# Iridium_9603_Beacon.net
KiCad netlist of a schematic drawn in EAGLE
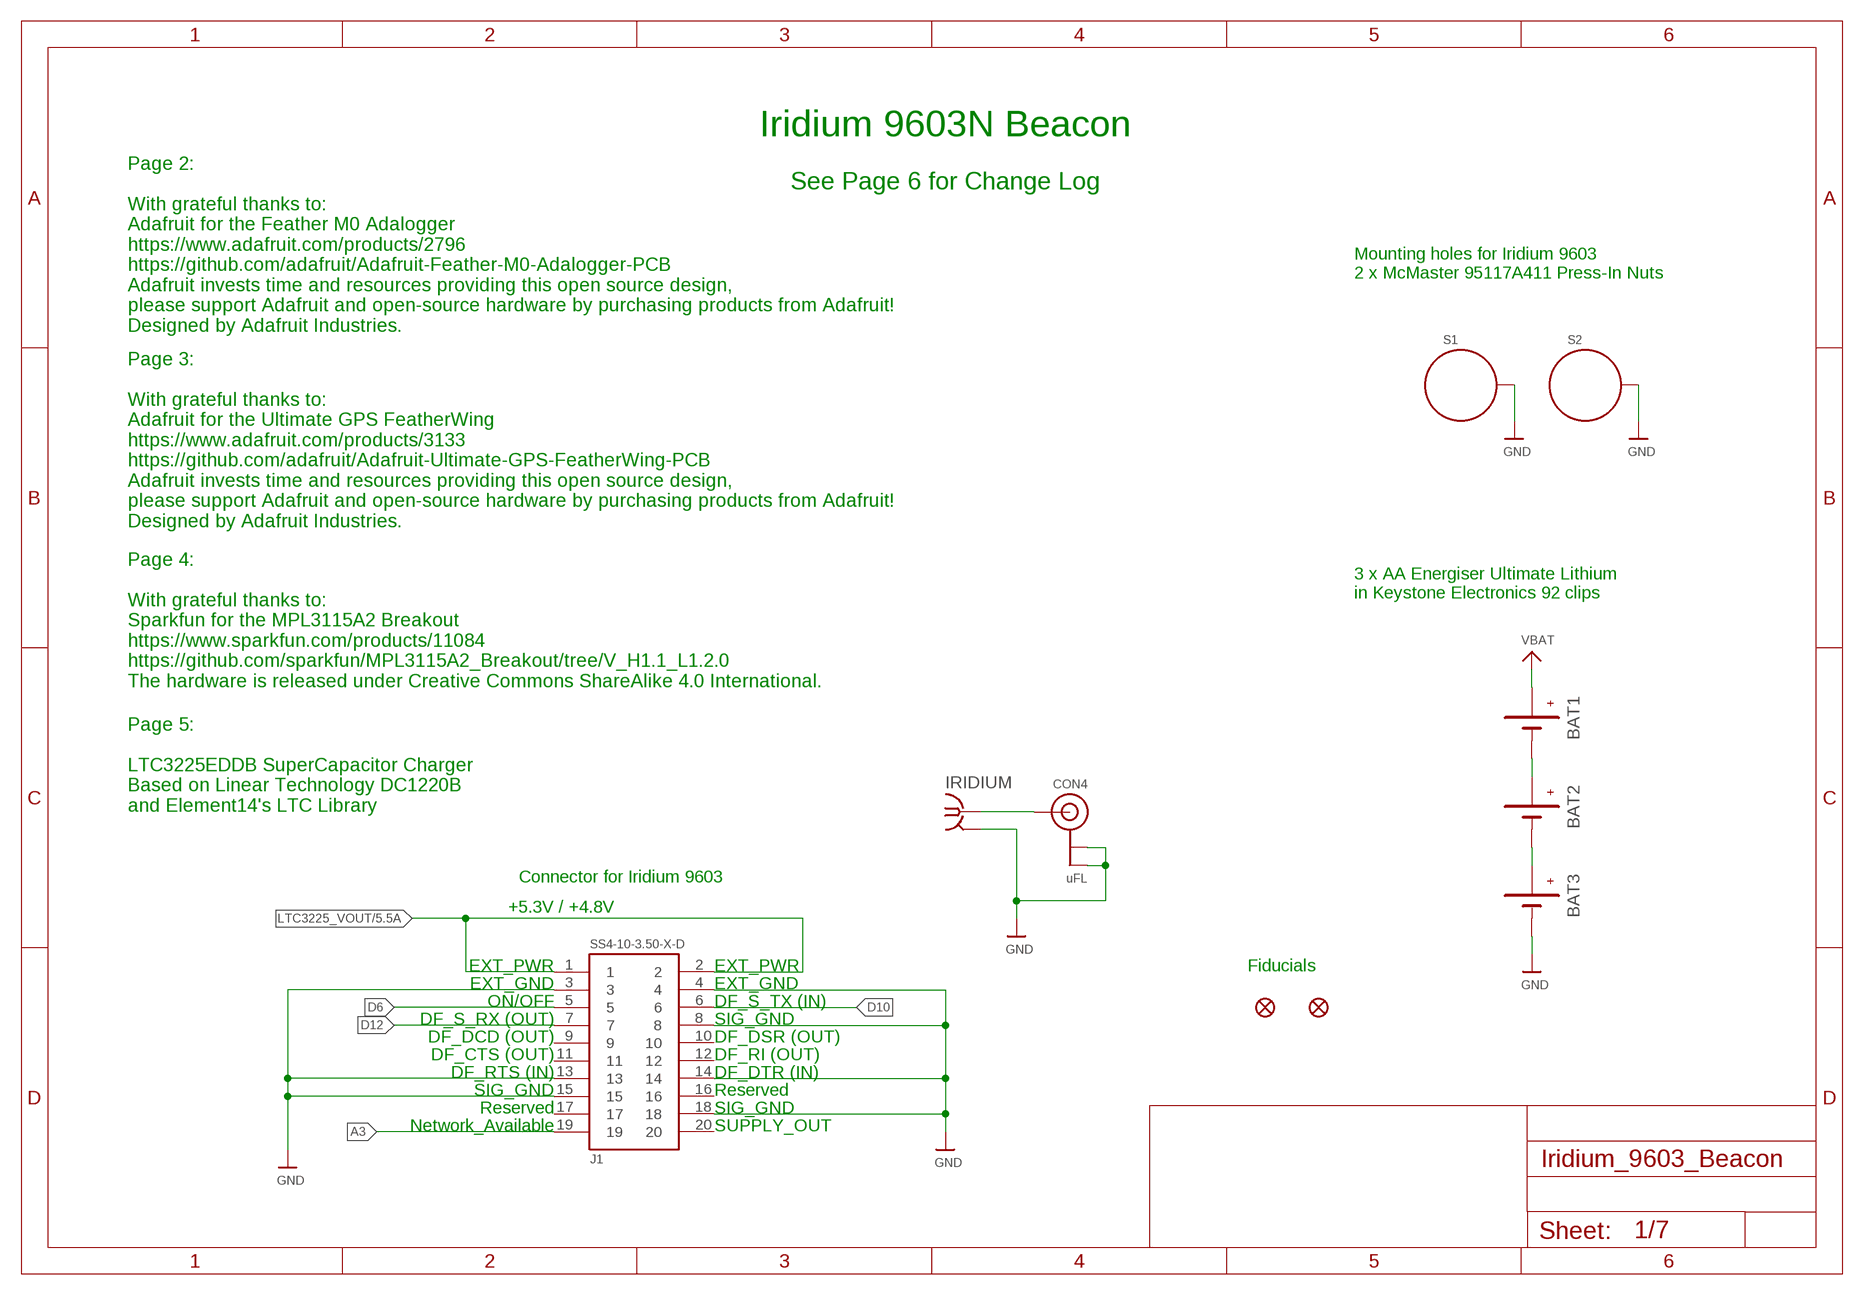
[diagram p0: schematic, sheet 1]
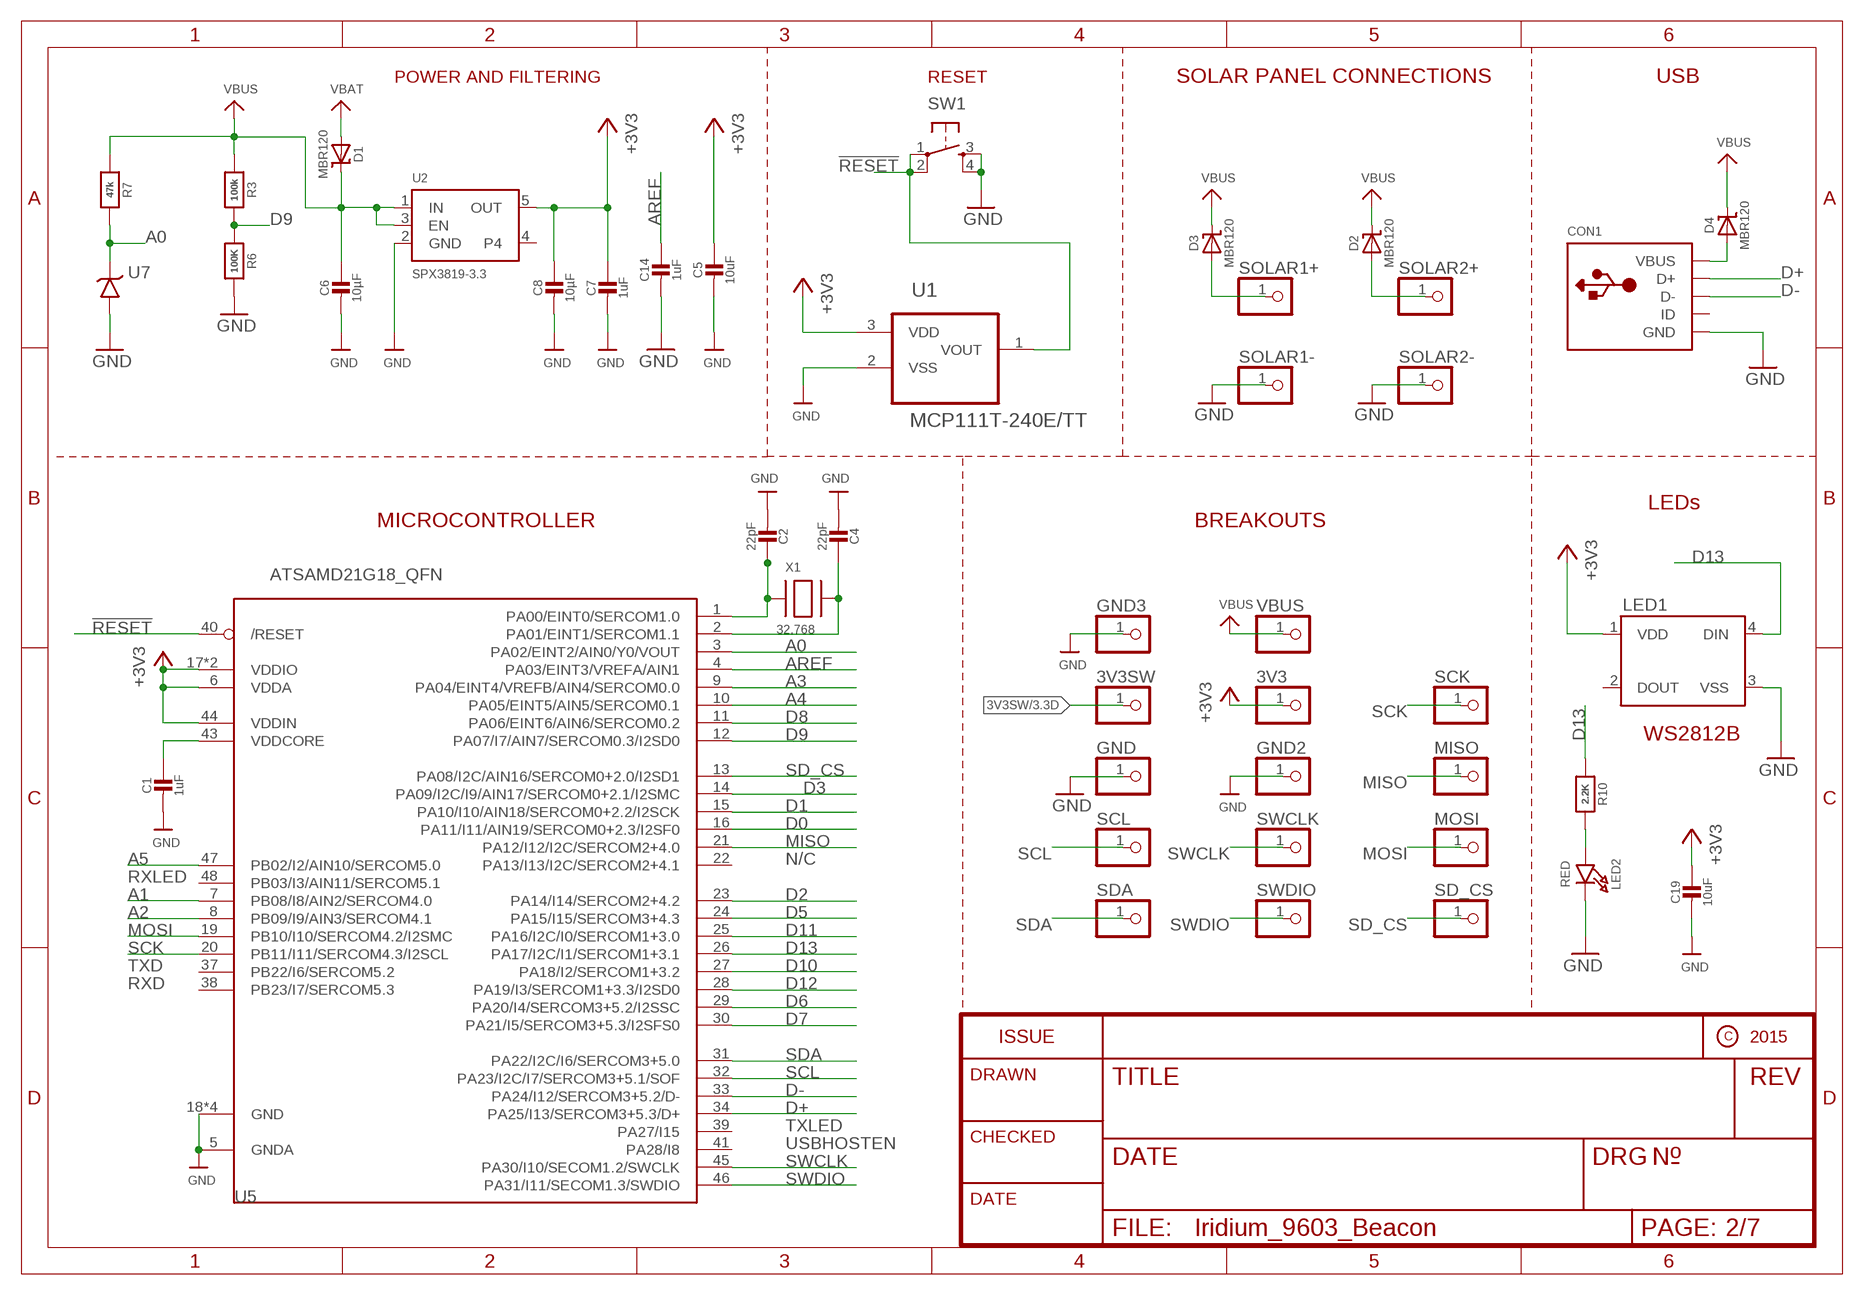
[diagram p1: schematic, sheet 2]
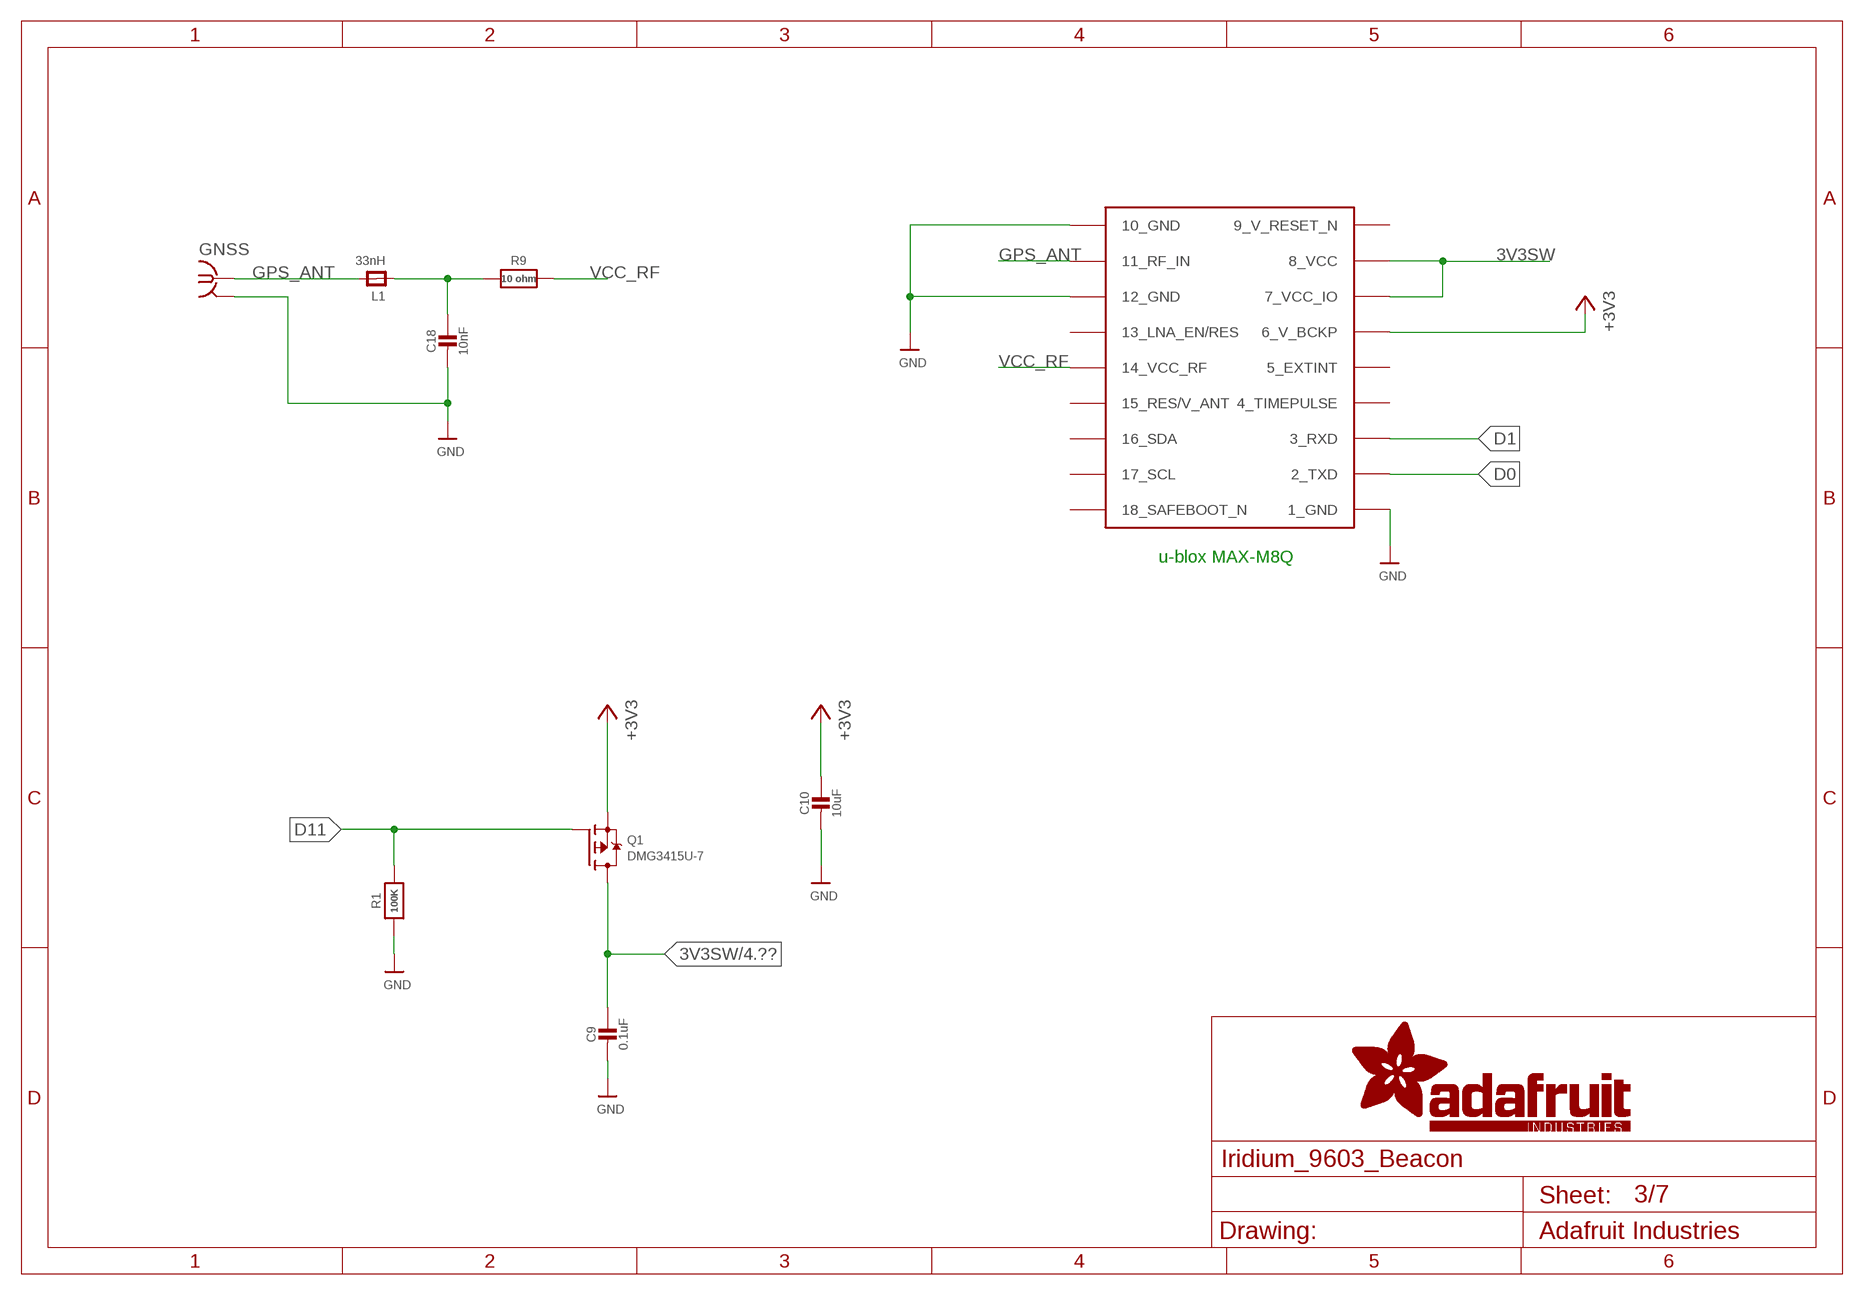
[diagram p2: schematic, sheet 3]
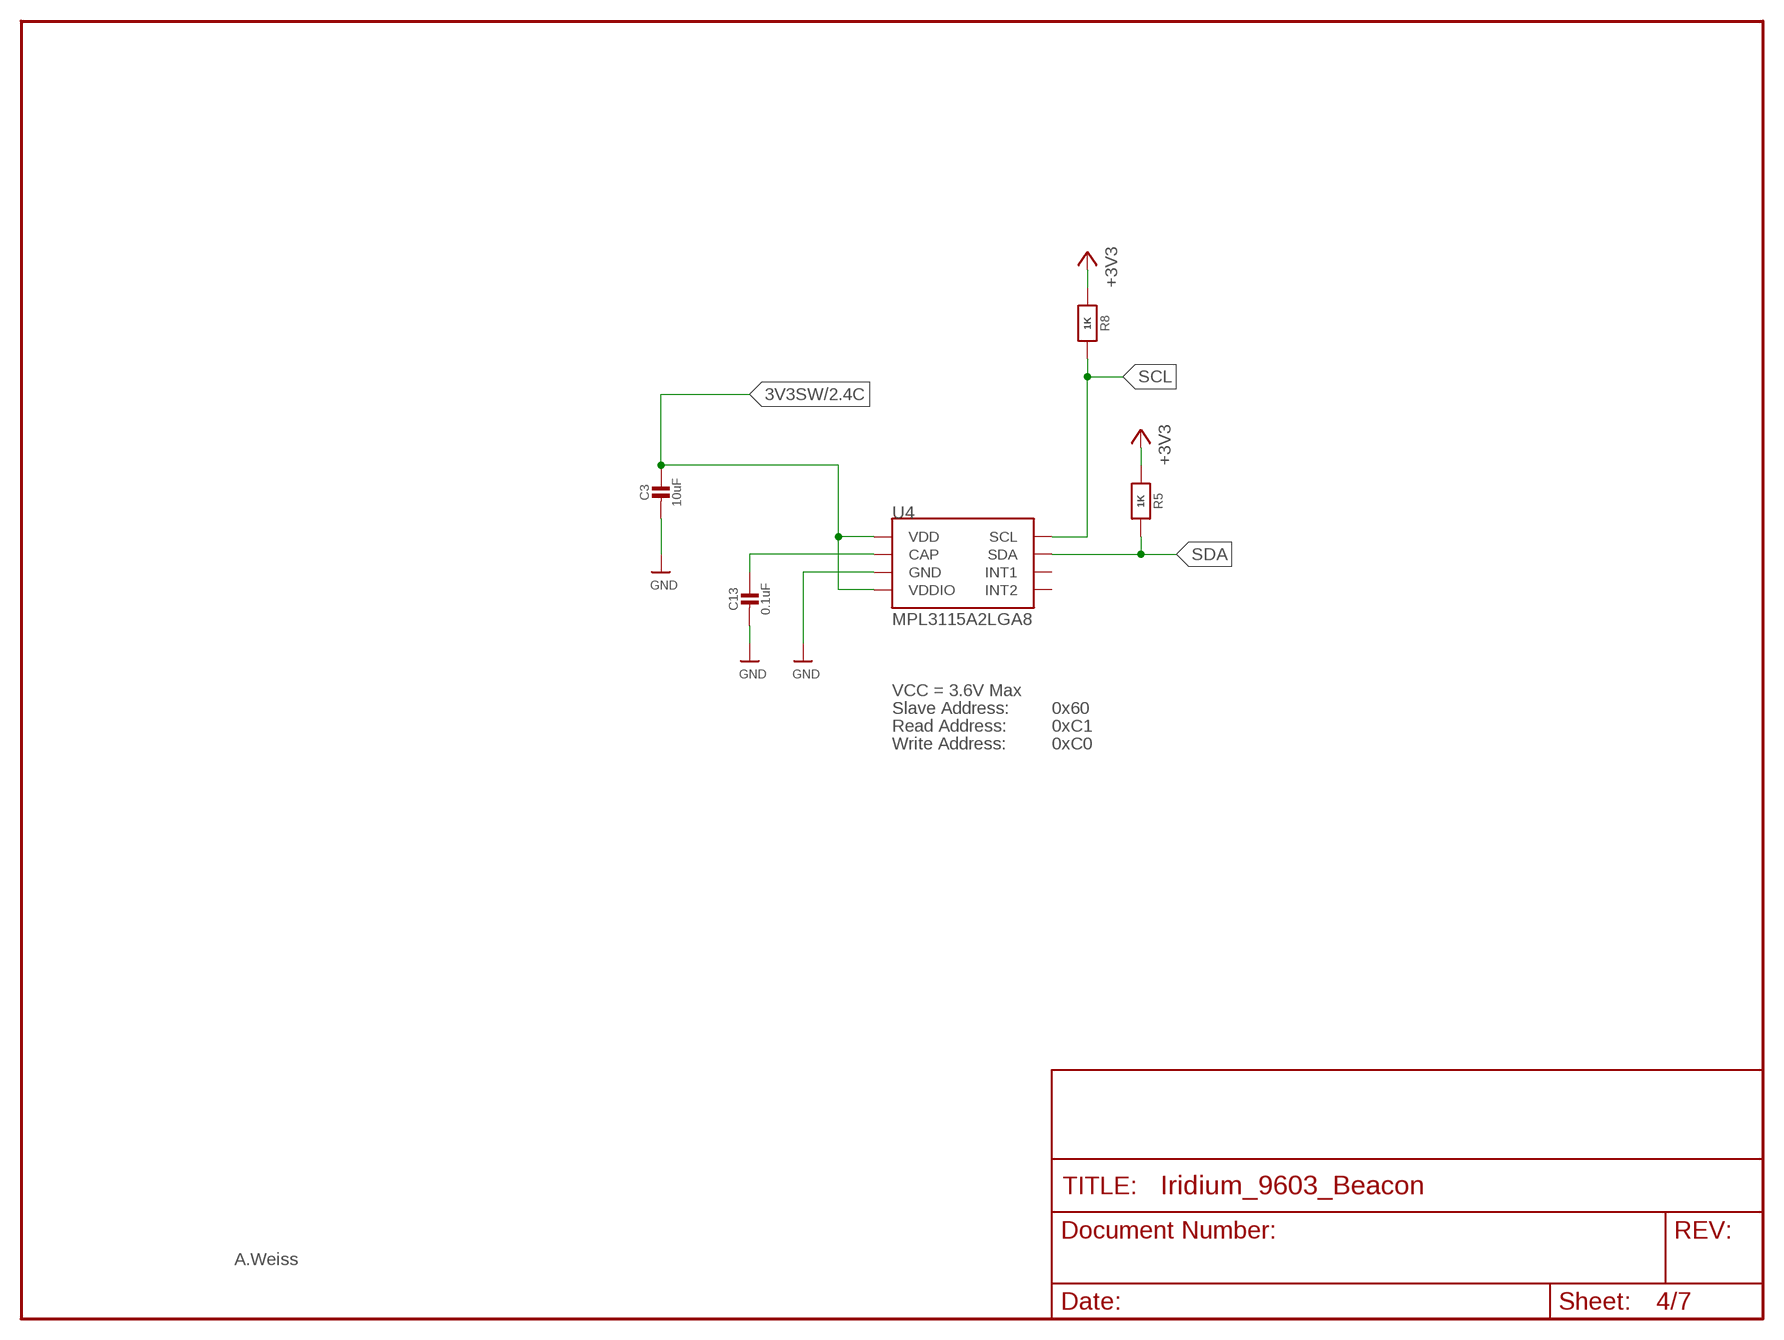
[diagram p3: schematic, sheet 4]
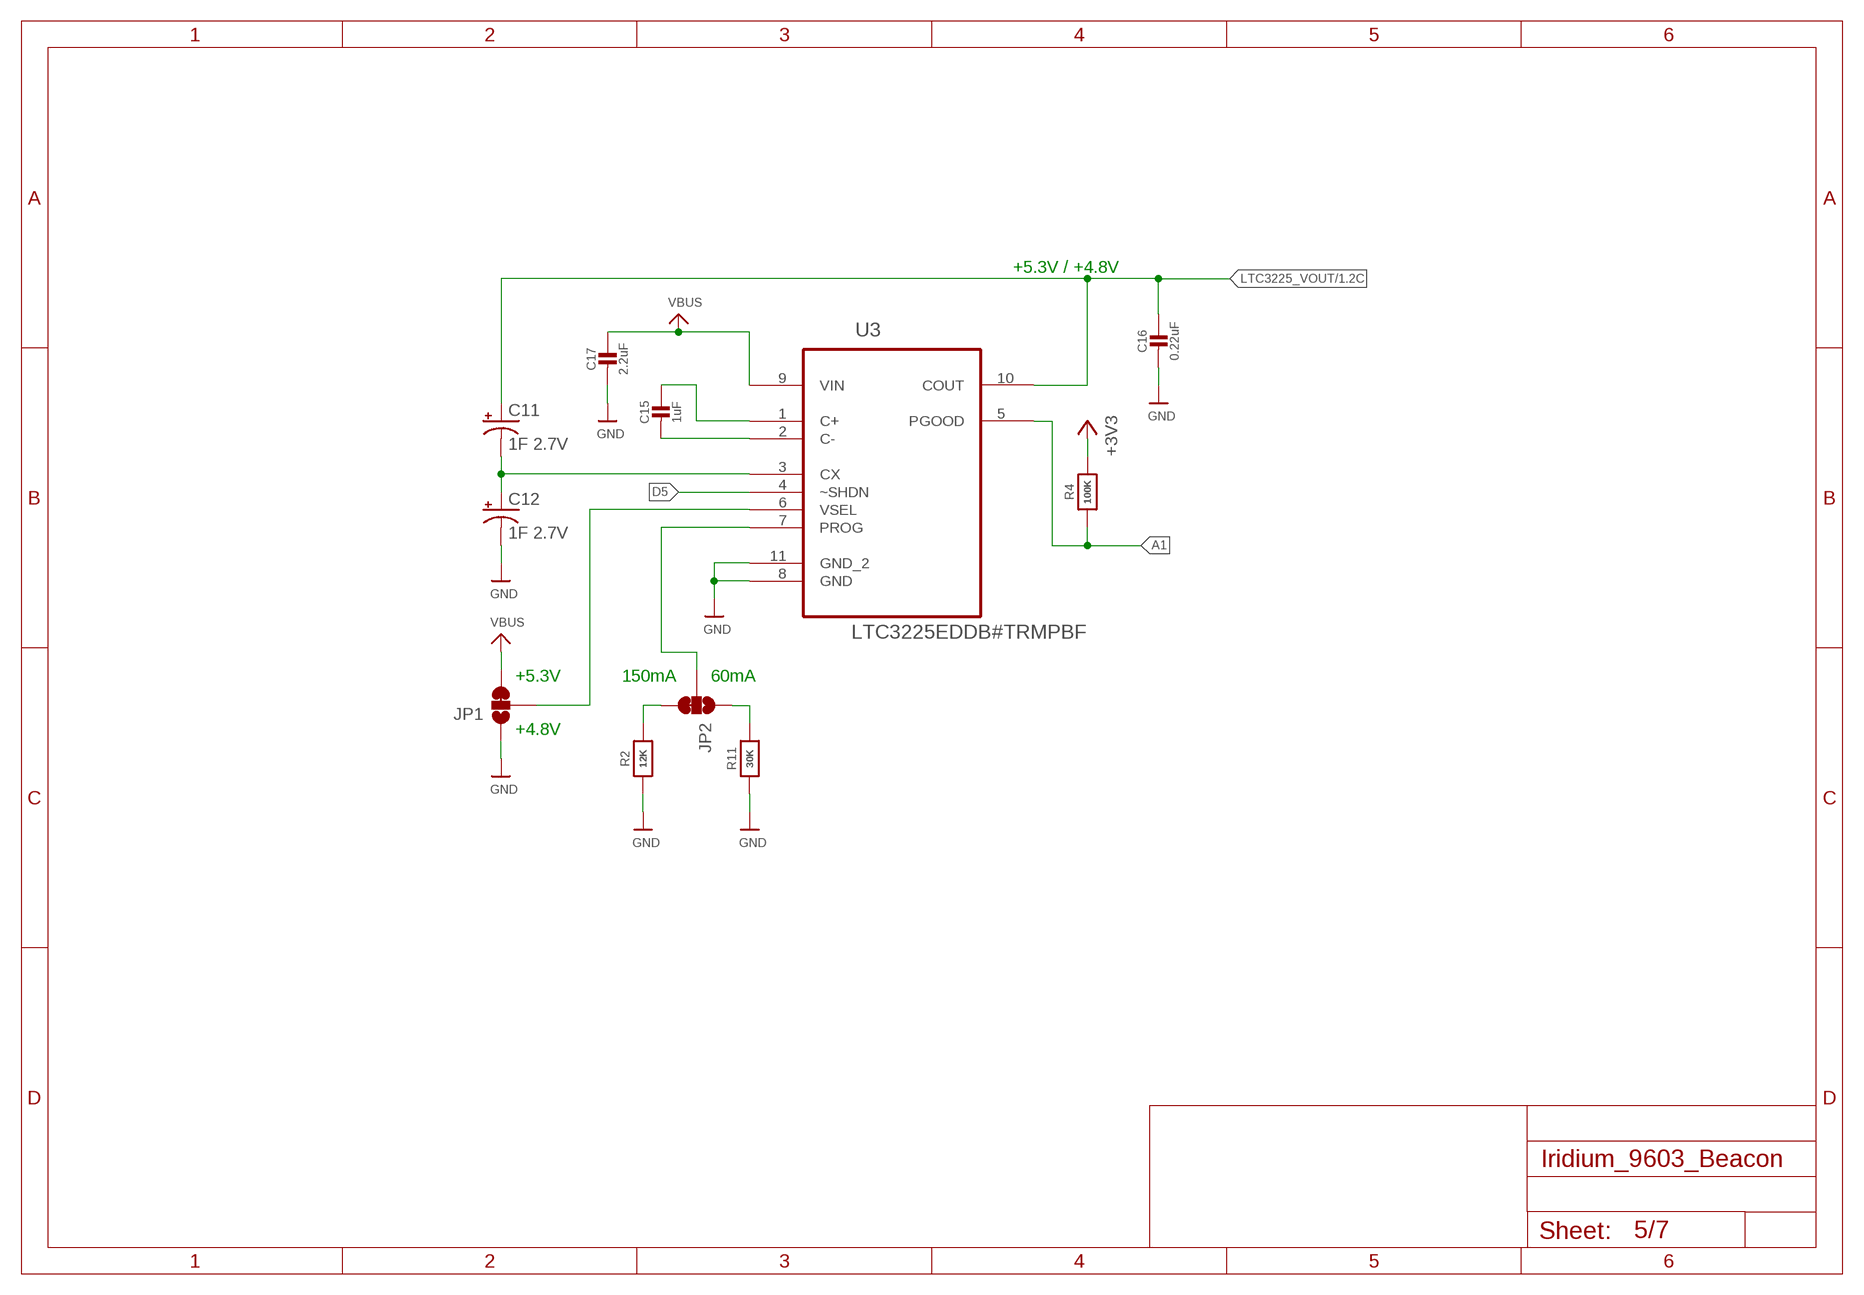
[diagram p4: schematic, sheet 5]
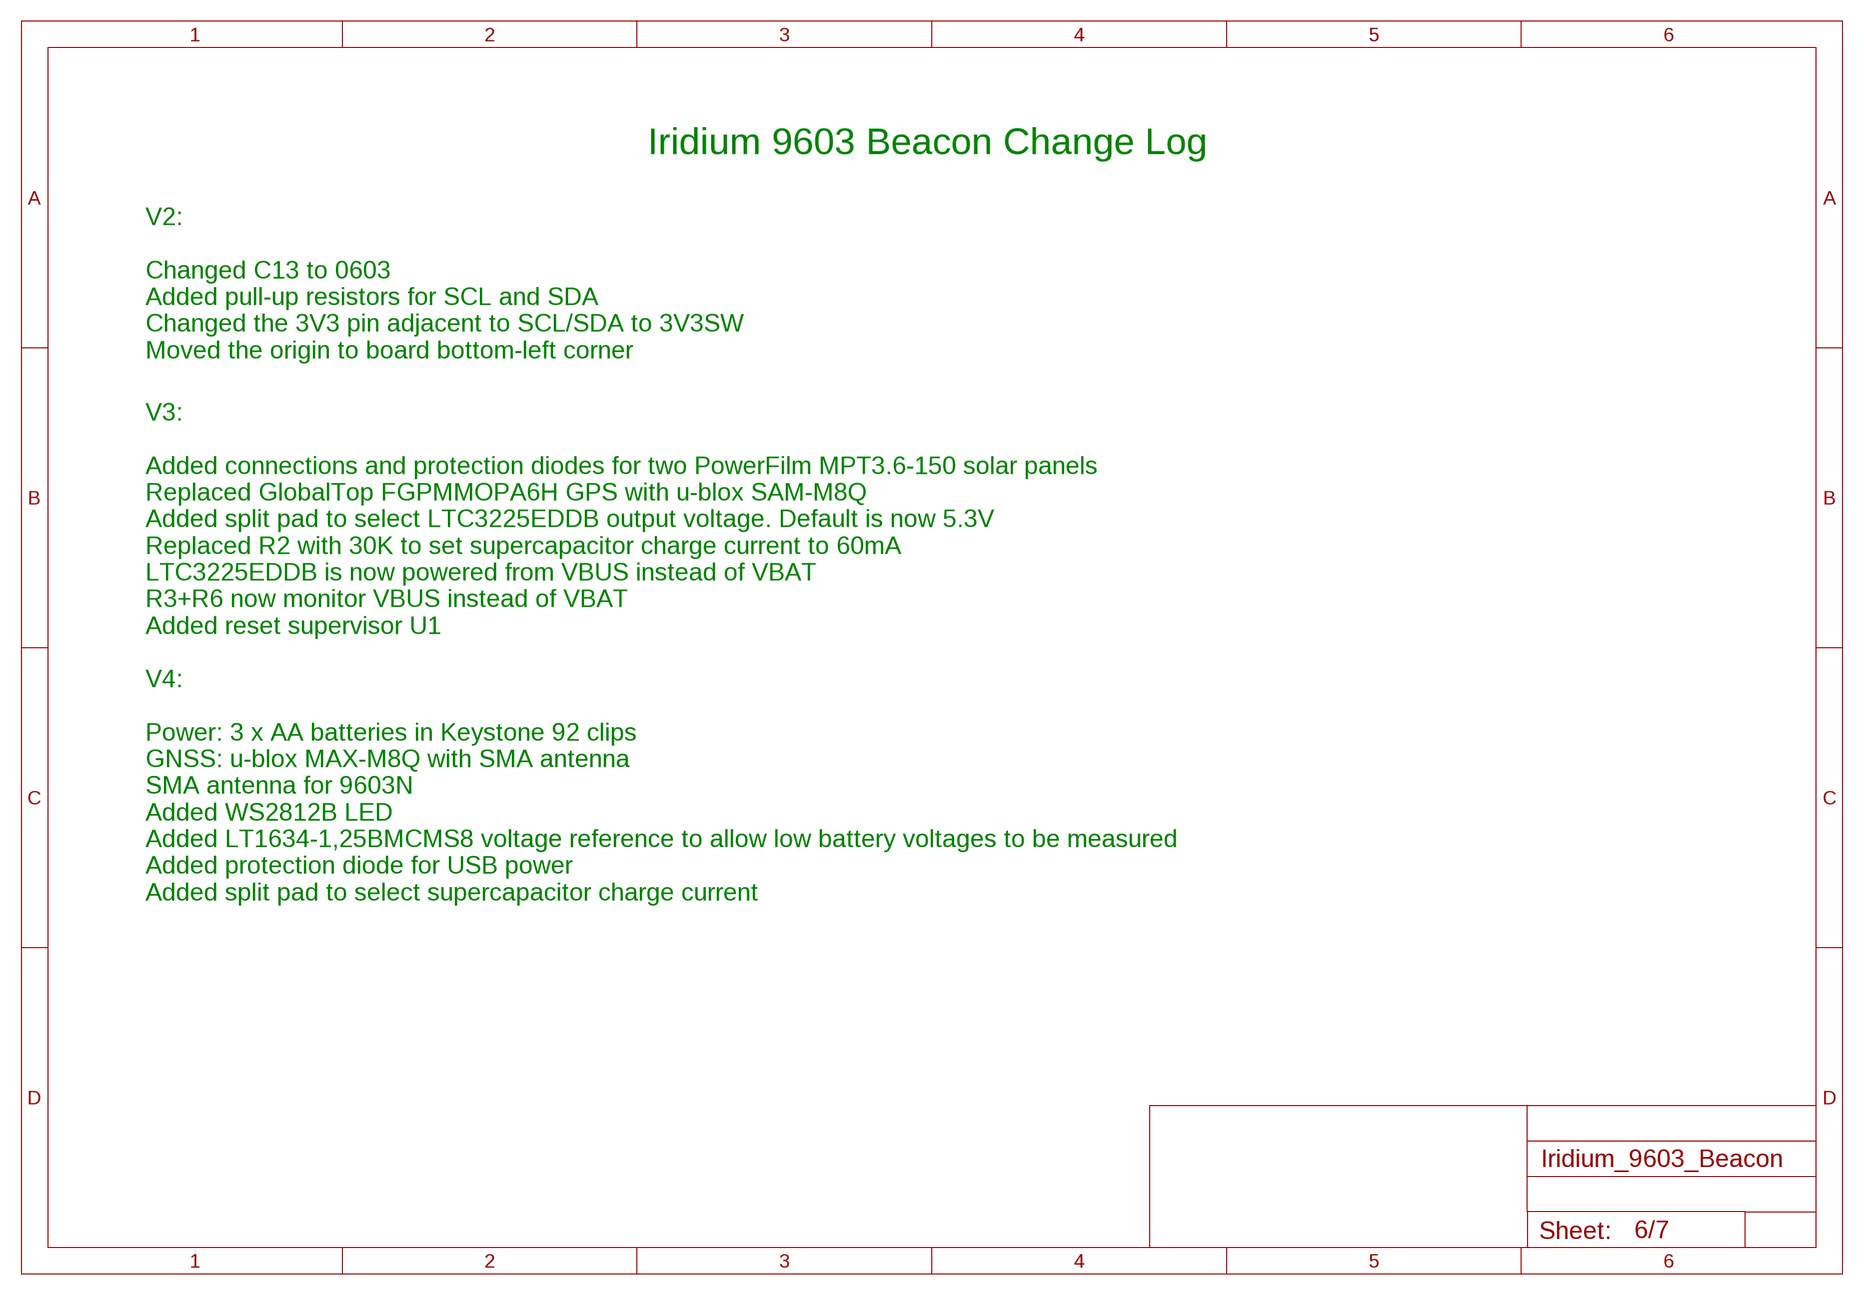
[diagram p5: schematic, sheet 6]
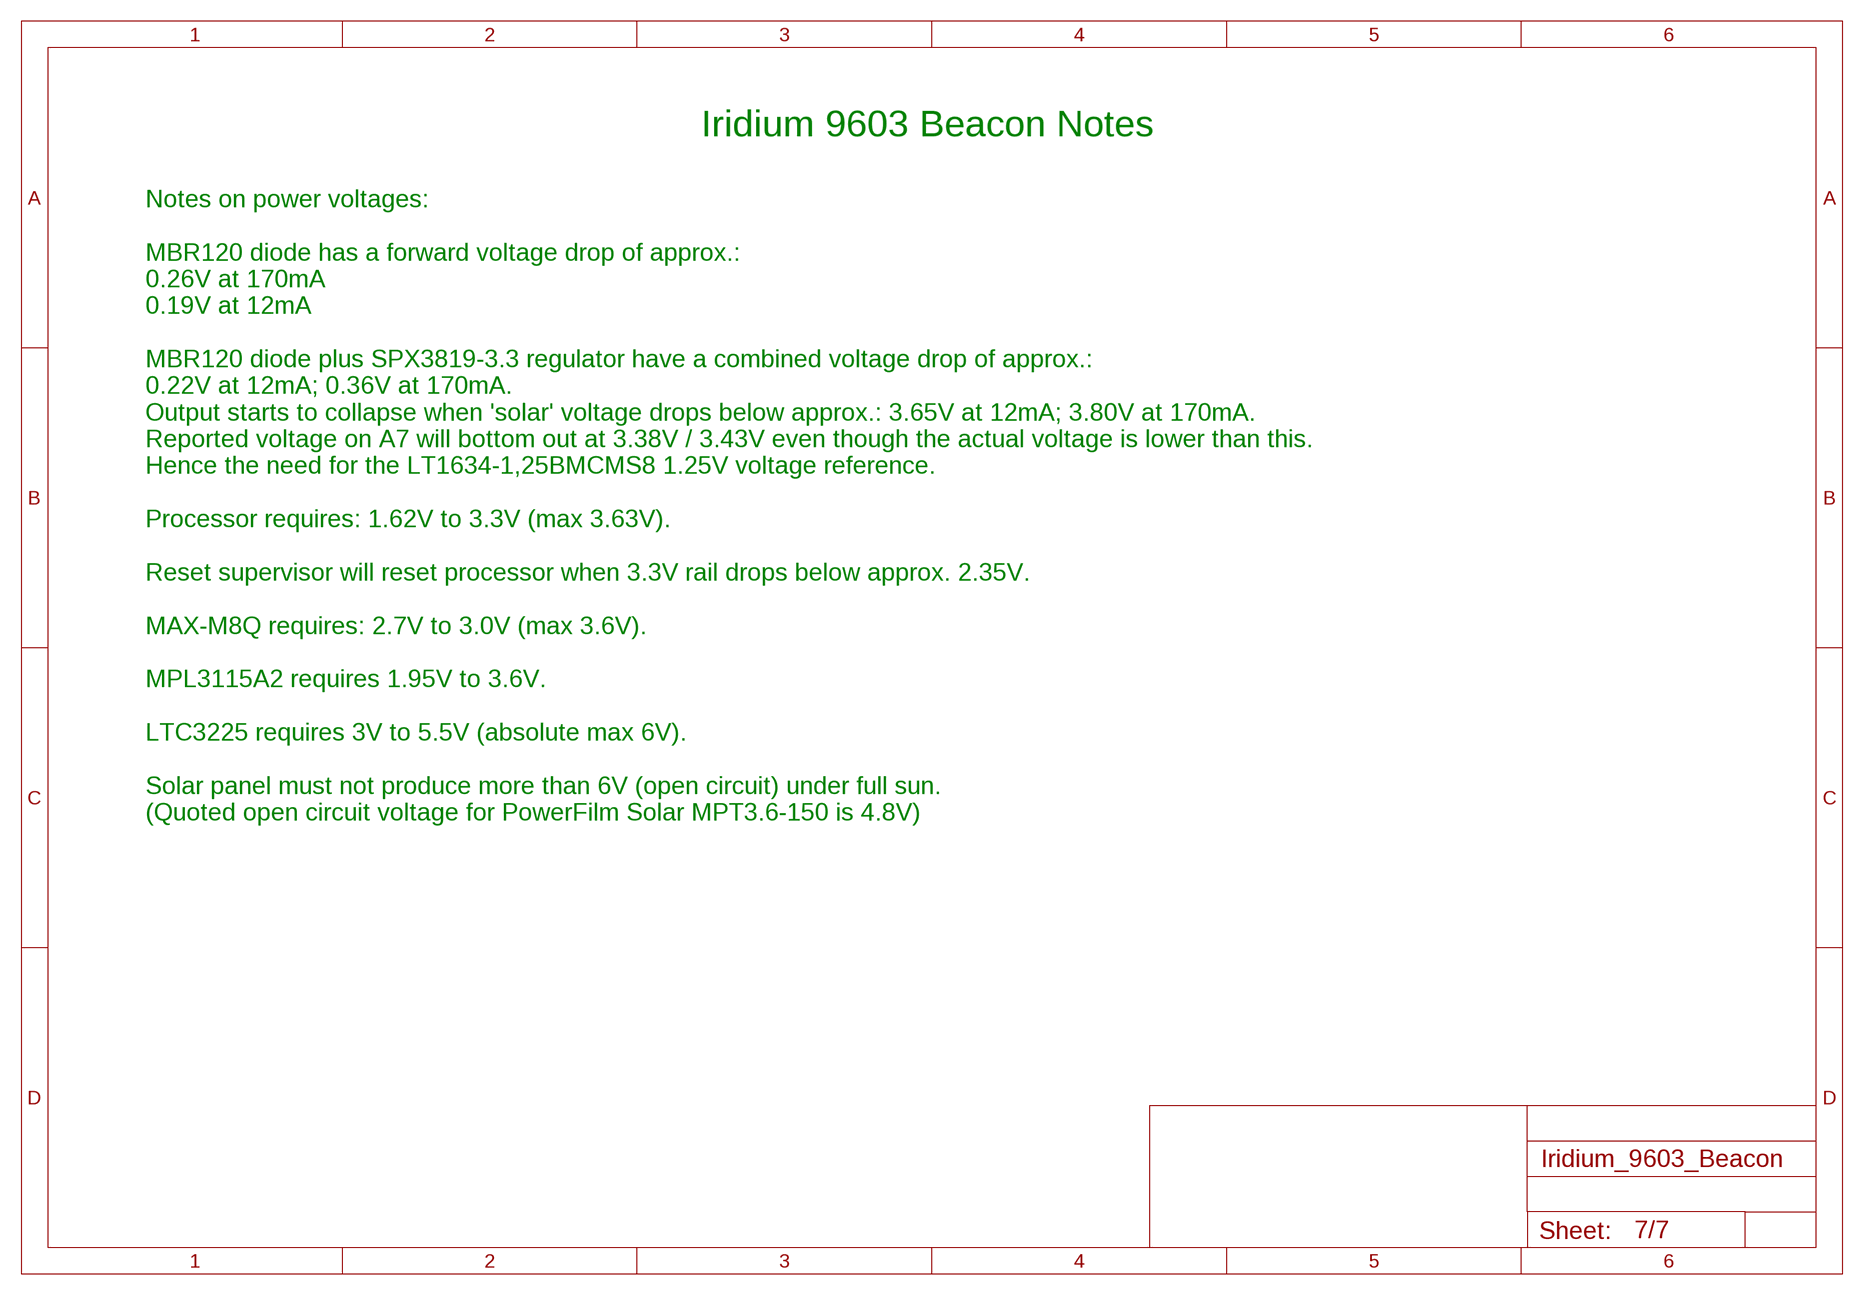
[diagram p6: schematic, sheet 7]

(export (version "E")
  (design (tool "Eeschema 10.0.6"))
  (components
    (comp (ref "3V3")
      (value "PINHD-1X1")
      (footprint "eagle-import:1X01")
      (libsource (lib "eagle-import") (part "PINHD-1X1"))
    )
    (comp (ref "3V3SW")
      (value "PINHD-1X1")
      (footprint "eagle-import:1X01")
      (libsource (lib "eagle-import") (part "PINHD-1X1"))
    )
    (comp (ref "C1")
      (value "1uF")
      (footprint "eagle-import:0603-NO")
      (libsource (lib "eagle-import") (part "CAP_CERAMIC0603_NO"))
    )
    (comp (ref "C2")
      (value "22pF")
      (footprint "eagle-import:0603-NO")
      (libsource (lib "eagle-import") (part "CAP_CERAMIC0603_NO"))
    )
    (comp (ref "C4")
      (value "22pF")
      (footprint "eagle-import:0603-NO")
      (libsource (lib "eagle-import") (part "CAP_CERAMIC0603_NO"))
    )
    (comp (ref "C5")
      (value "10uF")
      (footprint "eagle-import:0805-NO")
      (libsource (lib "eagle-import") (part "CAP_CERAMIC0805-NOOUTLINE"))
    )
    (comp (ref "C6")
      (value "10µF")
      (footprint "eagle-import:0805-NO")
      (libsource (lib "eagle-import") (part "CAP_CERAMIC0805-NOOUTLINE"))
    )
    (comp (ref "C7")
      (value "1uF")
      (footprint "eagle-import:0603-NO")
      (libsource (lib "eagle-import") (part "CAP_CERAMIC0603_NO"))
    )
    (comp (ref "C8")
      (value "10µF")
      (footprint "eagle-import:0805-NO")
      (libsource (lib "eagle-import") (part "CAP_CERAMIC0805-NOOUTLINE"))
    )
    (comp (ref "C14")
      (value "1uF")
      (footprint "eagle-import:0603-NO")
      (libsource (lib "eagle-import") (part "CAP_CERAMIC0603_NO"))
    )
    (comp (ref "C19")
      (value "10uF")
      (footprint "eagle-import:0805-NO")
      (libsource (lib "eagle-import") (part "CAP_CERAMIC0805-NOOUTLINE"))
    )
    (comp (ref "CON1")
      (value "USBFCI_10103594")
      (footprint "eagle-import:FCI_10103594")
      (libsource (lib "eagle-import") (part "USBFCI_10103594"))
    )
    (comp (ref "D1")
      (value "MBR120")
      (footprint "eagle-import:SOD-123")
      (libsource (lib "eagle-import") (part "DIODE-SCHOTTKYSOD-123"))
    )
    (comp (ref "D2")
      (value "MBR120")
      (footprint "eagle-import:SOD-123")
      (libsource (lib "eagle-import") (part "DIODE-SCHOTTKYSOD-123"))
    )
    (comp (ref "D3")
      (value "MBR120")
      (footprint "eagle-import:SOD-123")
      (libsource (lib "eagle-import") (part "DIODE-SCHOTTKYSOD-123"))
    )
    (comp (ref "D4")
      (value "MBR120")
      (footprint "eagle-import:SOD-123")
      (libsource (lib "eagle-import") (part "DIODE-SCHOTTKYSOD-123"))
    )
    (comp (ref "GND")
      (value "PINHD-1X1")
      (footprint "eagle-import:1X01")
      (libsource (lib "eagle-import") (part "PINHD-1X1"))
    )
    (comp (ref "GND2")
      (value "PINHD-1X1")
      (footprint "eagle-import:1X01")
      (libsource (lib "eagle-import") (part "PINHD-1X1"))
    )
    (comp (ref "GND3")
      (value "PINHD-1X1")
      (footprint "eagle-import:1X01")
      (libsource (lib "eagle-import") (part "PINHD-1X1"))
    )
    (comp (ref "LED1")
      (value "WS2812B")
      (footprint "eagle-import:WS2812B")
      (libsource (lib "eagle-import") (part "WS2812B"))
    )
    (comp (ref "LED2")
      (value "RED")
      (footprint "eagle-import:CHIPLED_0805_NOOUTLINE")
      (libsource (lib "eagle-import") (part "LED0805_NOOUTLINE"))
    )
    (comp (ref "MISO")
      (value "PINHD-1X1")
      (footprint "eagle-import:1X01")
      (libsource (lib "eagle-import") (part "PINHD-1X1"))
    )
    (comp (ref "MOSI")
      (value "PINHD-1X1")
      (footprint "eagle-import:1X01")
      (libsource (lib "eagle-import") (part "PINHD-1X1"))
    )
    (comp (ref "R3")
      (value "100k")
      (footprint "eagle-import:0603-NO")
      (libsource (lib "eagle-import") (part "RESISTOR_0603_NOOUT"))
    )
    (comp (ref "R6")
      (value "100K")
      (footprint "eagle-import:0603-NO")
      (libsource (lib "eagle-import") (part "RESISTOR_0603_NOOUT"))
    )
    (comp (ref "R7")
      (value "47k")
      (footprint "eagle-import:0603-NO")
      (libsource (lib "eagle-import") (part "RESISTOR_0603_NOOUT"))
    )
    (comp (ref "R10")
      (value "2.2K")
      (footprint "eagle-import:0603-NO")
      (libsource (lib "eagle-import") (part "RESISTOR_0603_NOOUT"))
    )
    (comp (ref "SCK")
      (value "PINHD-1X1")
      (footprint "eagle-import:1X01")
      (libsource (lib "eagle-import") (part "PINHD-1X1"))
    )
    (comp (ref "SCL")
      (value "PINHD-1X1")
      (footprint "eagle-import:1X01")
      (libsource (lib "eagle-import") (part "PINHD-1X1"))
    )
    (comp (ref "SDA")
      (value "PINHD-1X1")
      (footprint "eagle-import:1X01")
      (libsource (lib "eagle-import") (part "PINHD-1X1"))
    )
    (comp (ref "SD_CS")
      (value "PINHD-1X1")
      (footprint "eagle-import:1X01")
      (libsource (lib "eagle-import") (part "PINHD-1X1"))
    )
    (comp (ref "SOLAR1+")
      (value "PINHD-1X1")
      (footprint "eagle-import:1X01")
      (libsource (lib "eagle-import") (part "PINHD-1X1"))
    )
    (comp (ref "SOLAR1-")
      (value "PINHD-1X1")
      (footprint "eagle-import:1X01")
      (libsource (lib "eagle-import") (part "PINHD-1X1"))
    )
    (comp (ref "SOLAR2+")
      (value "PINHD-1X1")
      (footprint "eagle-import:1X01")
      (libsource (lib "eagle-import") (part "PINHD-1X1"))
    )
    (comp (ref "SOLAR2-")
      (value "PINHD-1X1")
      (footprint "eagle-import:1X01")
      (libsource (lib "eagle-import") (part "PINHD-1X1"))
    )
    (comp (ref "SW1")
      (value "SWITCH_SPST_4_PINRECT")
      (footprint "eagle-import:TACTILE_SWITCH_SMD_4.6X2.8MM")
      (libsource (lib "eagle-import") (part "SWITCH_SPST_4_PINRECT"))
    )
    (comp (ref "SWCLK")
      (value "PINHD-1X1")
      (footprint "eagle-import:1X01")
      (libsource (lib "eagle-import") (part "PINHD-1X1"))
    )
    (comp (ref "SWDIO")
      (value "PINHD-1X1")
      (footprint "eagle-import:1X01")
      (libsource (lib "eagle-import") (part "PINHD-1X1"))
    )
    (comp (ref "U1")
      (value "MCP111T-240E/TT")
      (footprint "eagle-import:SOT95P237X112-3N")
      (fields (field (name "MPN") "MCP111T-270E/TT") (field (name "MPN_1") "MCP111T-240E/TT"))
      (libsource (lib "eagle-import") (part "MCP111T-270E/TT"))
    )
    (comp (ref "U2")
      (value "SPX3819-3.3")
      (footprint "eagle-import:SOT23-5")
      (libsource (lib "eagle-import") (part "VREG_SOT23-5"))
    )
    (comp (ref "U5")
      (value "ATSAMD21G18_QFN")
      (footprint "eagle-import:TQFN48_7MM")
      (libsource (lib "eagle-import") (part "ATSAMD21J_QFN"))
    )
    (comp (ref "U7")
      (value "LT1634-1,25BMCMS8")
      (footprint "eagle-import:MSOP8")
      (libsource (lib "eagle-import") (part "LT1634BMCMS8-1,25"))
    )
    (comp (ref "VBUS")
      (value "PINHD-1X1")
      (footprint "eagle-import:1X01")
      (libsource (lib "eagle-import") (part "PINHD-1X1"))
    )
    (comp (ref "X1")
      (value "32.768")
      (footprint "eagle-import:XTAL3215")
      (libsource (lib "eagle-import") (part "XTAL-3.2X1.5"))
    )
    (comp (ref "BAT1")
      (value "BATTERYKEYSTONE92")
      (footprint "eagle-import:BATTERY-AAA-KEYSTONE92")
      (libsource (lib "eagle-import") (part "BATTERYKEYSTONE92"))
    )
    (comp (ref "BAT2")
      (value "BATTERYKEYSTONE92")
      (footprint "eagle-import:BATTERY-AAA-KEYSTONE92")
      (libsource (lib "eagle-import") (part "BATTERYKEYSTONE92"))
    )
    (comp (ref "BAT3")
      (value "BATTERYKEYSTONE92")
      (footprint "eagle-import:BATTERY-AAA-KEYSTONE92")
      (libsource (lib "eagle-import") (part "BATTERYKEYSTONE92"))
    )
    (comp (ref "CON4")
      (value "uFL")
      (footprint "eagle-import:U.FL")
      (libsource (lib "eagle-import") (part "ANTENNA_U.FL"))
    )
    (comp (ref "FD1")
      (value "FIDUCIAL1X2")
      (footprint "eagle-import:FIDUCIAL-1X2")
      (libsource (lib "eagle-import") (part "FIDUCIAL1X2"))
    )
    (comp (ref "FD2")
      (value "FIDUCIAL1X2")
      (footprint "eagle-import:FIDUCIAL-1X2")
      (libsource (lib "eagle-import") (part "FIDUCIAL1X2"))
    )
    (comp (ref "IRIDIUM")
      (value "SMA-142-0711-821/826")
      (footprint "eagle-import:J502-ND-142-0711-821_826")
      (fields (field (name "MF") "JOHNSON COMPONENTS") (field (name "MPN") "142-0711-821"))
      (libsource (lib "eagle-import") (part "con-coax_133_SMA-142-0711-821/826"))
    )
    (comp (ref "J1")
      (value "SS4-10-3.50-X-D")
      (footprint "eagle-import:SS4-10-3.50-X-D")
      (libsource (lib "eagle-import") (part "SS4-10-3.50-X-D"))
    )
    (comp (ref "S1")
      (value "STANDOFF_ELECTRICALMCMASTER-95117A411")
      (footprint "eagle-import:STANDOFF-ELECTRICAL-MCMASTER-95117A411")
      (libsource (lib "eagle-import") (part "STANDOFF_ELECTRICALMCMASTER-95117A411"))
    )
    (comp (ref "S2")
      (value "STANDOFF_ELECTRICALMCMASTER-95117A411")
      (footprint "eagle-import:STANDOFF-ELECTRICAL-MCMASTER-95117A411")
      (libsource (lib "eagle-import") (part "STANDOFF_ELECTRICALMCMASTER-95117A411"))
    )
    (comp (ref "C9")
      (value "0.1uF")
      (footprint "eagle-import:0805-NO")
      (libsource (lib "eagle-import") (part "CAP_CERAMIC0805-NOOUTLINE"))
    )
    (comp (ref "C10")
      (value "10uF")
      (footprint "eagle-import:0805-NO")
      (libsource (lib "eagle-import") (part "CAP_CERAMIC0805-NOOUTLINE"))
    )
    (comp (ref "C18")
      (value "10nF")
      (footprint "eagle-import:0805-NO")
      (libsource (lib "eagle-import") (part "CAP_CERAMIC0805-NOOUTLINE"))
    )
    (comp (ref "GNSS")
      (value "SMA-142-0711-821/826")
      (footprint "eagle-import:J502-ND-142-0711-821_826")
      (fields (field (name "MF") "JOHNSON COMPONENTS") (field (name "MPN") "142-0711-821"))
      (libsource (lib "eagle-import") (part "SMA-142-0711-821/826"))
    )
    (comp (ref "L1")
      (value "33nH")
      (footprint "eagle-import:0805-NO")
      (libsource (lib "eagle-import") (part "FERRITE-0805NO"))
    )
    (comp (ref "Q1")
      (value "DMG3415U-7")
      (footprint "eagle-import:SOT23-WIDE")
      (libsource (lib "eagle-import") (part "MOSFET-PWIDE"))
    )
    (comp (ref "R1")
      (value "100K")
      (footprint "eagle-import:0805-NO")
      (libsource (lib "eagle-import") (part "RESISTOR0805_NOOUTLINE"))
    )
    (comp (ref "R9")
      (value "10 ohm")
      (footprint "eagle-import:0805-NO")
      (libsource (lib "eagle-import") (part "RESISTOR0805_NOOUTLINE"))
    )
    (comp (ref "U6")
      (value "MAX-M8")
      (footprint "eagle-import:MAX-M8")
      (libsource (lib "eagle-import") (part "MAX-M8"))
    )
    (comp (ref "C3")
      (value "10uF")
      (footprint "eagle-import:0805-NO")
      (libsource (lib "eagle-import") (part "CAP_CERAMIC0805-NOOUTLINE"))
    )
    (comp (ref "C13")
      (value "0.1uF")
      (footprint "eagle-import:0603-NO")
      (libsource (lib "eagle-import") (part "CAP_CERAMIC0603_NO"))
    )
    (comp (ref "R5")
      (value "1K")
      (footprint "eagle-import:0603-NO")
      (libsource (lib "eagle-import") (part "RESISTOR_0603_NOOUT"))
    )
    (comp (ref "R8")
      (value "1K")
      (footprint "eagle-import:0603-NO")
      (libsource (lib "eagle-import") (part "RESISTOR_0603_NOOUT"))
    )
    (comp (ref "U4")
      (value "MPL3115A2LGA8")
      (footprint "eagle-import:LGA8")
      (libsource (lib "eagle-import") (part "MPL3115A2LGA8"))
    )
    (comp (ref "C11")
      (value "1F 2.7V")
      (footprint "eagle-import:CPOL-RADIAL-1F-2.7V")
      (libsource (lib "eagle-import") (part "1F-2.7V(PTH)CPOL-RADIAL-1H-2.7V"))
    )
    (comp (ref "C12")
      (value "1F 2.7V")
      (footprint "eagle-import:CPOL-RADIAL-1F-2.7V")
      (libsource (lib "eagle-import") (part "1F-2.7V(PTH)CPOL-RADIAL-1H-2.7V"))
    )
    (comp (ref "C15")
      (value "1uF")
      (footprint "eagle-import:0603-NO")
      (libsource (lib "eagle-import") (part "CAP_CERAMIC0603_NO"))
    )
    (comp (ref "C16")
      (value "0.22uF")
      (footprint "eagle-import:0603-NO")
      (libsource (lib "eagle-import") (part "CAP_CERAMIC0603_NO"))
    )
    (comp (ref "C17")
      (value "2.2uF")
      (footprint "eagle-import:0805-NO")
      (libsource (lib "eagle-import") (part "CAP_CERAMIC0805-NOOUTLINE"))
    )
    (comp (ref "JP1")
      (value "JUMPER-PAD-3-2OF3_NC_BY_TRACE_LARGE")
      (footprint "eagle-import:PAD-JUMPER-3-2OF3_NC_BY_TRACE_YES_SILK_LARGE")
      (libsource (lib "eagle-import") (part "JUMPER-PAD-3-2OF3_NC_BY_TRACE_LARGE"))
    )
    (comp (ref "JP2")
      (value "JUMPER-PAD-3-2OF3_NC_BY_TRACE_LARGE")
      (footprint "eagle-import:PAD-JUMPER-3-2OF3_NC_BY_TRACE_YES_SILK_LARGE")
      (libsource (lib "eagle-import") (part "JUMPER-PAD-3-2OF3_NC_BY_TRACE_LARGE"))
    )
    (comp (ref "R2")
      (value "12K")
      (footprint "eagle-import:0805-NO")
      (libsource (lib "eagle-import") (part "RESISTOR0805_NOOUTLINE"))
    )
    (comp (ref "R4")
      (value "100K")
      (footprint "eagle-import:0805-NO")
      (libsource (lib "eagle-import") (part "RESISTOR0805_NOOUTLINE"))
    )
    (comp (ref "R11")
      (value "30K")
      (footprint "eagle-import:0805-NO")
      (libsource (lib "eagle-import") (part "RESISTOR0805_NOOUTLINE"))
    )
    (comp (ref "U3")
      (value "LTC3225EDDB#TRMPBF")
      (footprint "eagle-import:DFN300X200-10L")
      (libsource (lib "eagle-import") (part "LTC3225EDDB-TRMPBFDFN300X200-10L"))
    )
  )
  (nets
    (net (code "1") (name "+3V3") (class "Default")
      (node (ref "3V3") (pin "1") (pinfunction "1_1") (pintype "passive"))
      (node (ref "C10") (pin "1") (pinfunction "1_1") (pintype "passive"))
      (node (ref "C19") (pin "1") (pinfunction "1_1") (pintype "passive"))
      (node (ref "C5") (pin "1") (pinfunction "1_1") (pintype "passive"))
      (node (ref "C7") (pin "1") (pinfunction "1_1") (pintype "passive"))
      (node (ref "C8") (pin "1") (pinfunction "1_1") (pintype "passive"))
      (node (ref "LED1") (pin "1") (pinfunction "VDD_1") (pintype "power_in"))
      (node (ref "Q1") (pin "2") (pinfunction "S_2") (pintype "passive"))
      (node (ref "R4") (pin "2") (pinfunction "2_2") (pintype "passive"))
      (node (ref "R5") (pin "1") (pinfunction "1_1") (pintype "passive"))
      (node (ref "R8") (pin "1") (pinfunction "1_1") (pintype "passive"))
      (node (ref "U1") (pin "3") (pinfunction "VDD_3") (pintype "power_in"))
      (node (ref "U2") (pin "5") (pinfunction "OUT_5") (pintype "power_in"))
      (node (ref "U5") (pin "17") (pinfunction "VDDIO_17") (pintype "power_in"))
      (node (ref "U5") (pin "36") (pinfunction "VDDIO_36") (pintype "power_in"))
      (node (ref "U5") (pin "44") (pinfunction "VDDIN_44") (pintype "power_in"))
      (node (ref "U5") (pin "6") (pinfunction "VDDA_6") (pintype "power_in"))
      (node (ref "U6") (pin "6_V_BCKP") (pinfunction "6_V_BCKP_6_V_BCKP") (pintype "bidirectional"))
    )
    (net (code "2") (name "3V3SW") (class "Default")
      (node (ref "3V3SW") (pin "1") (pinfunction "1_1") (pintype "passive"))
      (node (ref "C3") (pin "1") (pinfunction "1_1") (pintype "passive"))
      (node (ref "C9") (pin "1") (pinfunction "1_1") (pintype "passive"))
      (node (ref "Q1") (pin "3") (pinfunction "D_3") (pintype "passive"))
      (node (ref "U4") (pin "1") (pinfunction "VDD_1") (pintype "power_in"))
      (node (ref "U4") (pin "4") (pinfunction "VDDIO_4") (pintype "power_in"))
      (node (ref "U6") (pin "7_VCC_IO") (pinfunction "7_VCC_IO_7_VCC_IO") (pintype "power_in"))
      (node (ref "U6") (pin "8_VCC") (pinfunction "8_VCC_8_VCC") (pintype "power_in"))
    )
    (net (code "3") (name "9_V_RESET_N") (class "Default")
      (node (ref "U6") (pin "9_RESET_N") (pinfunction "9_V_RESET_N_9_RESET_N") (pintype "power_in"))
    )
    (net (code "4") (name "A0") (class "Default")
      (node (ref "R7") (pin "2") (pinfunction "2_2") (pintype "passive"))
      (node (ref "U5") (pin "3") (pinfunction "PA02/EINT2/AIN0/Y0/VOUT_3") (pintype "bidirectional"))
      (node (ref "U7") (pin "6") (pinfunction "VOUT_6") (pintype "passive"))
    )
    (net (code "5") (name "A1") (class "Default")
      (node (ref "R4") (pin "1") (pinfunction "1_1") (pintype "passive"))
      (node (ref "U3") (pin "5") (pinfunction "PGOOD_5") (pintype "output"))
      (node (ref "U5") (pin "7") (pinfunction "PB08/I8/AIN2/SERCOM4.0_7") (pintype "bidirectional"))
    )
    (net (code "6") (name "A2") (class "Default")
      (node (ref "U5") (pin "8") (pinfunction "PB09/I9/AIN3/SERCOM4.1_8") (pintype "bidirectional"))
    )
    (net (code "7") (name "A3") (class "Default")
      (node (ref "J1") (pin "19") (pinfunction "19_19") (pintype "bidirectional"))
      (node (ref "U5") (pin "9") (pinfunction "PA04/EINT4/VREFB/AIN4/SERCOM0.0_9") (pintype "bidirectional"))
    )
    (net (code "8") (name "A4") (class "Default")
      (node (ref "U5") (pin "10") (pinfunction "PA05/EINT5/AIN5/SERCOM0.1_10") (pintype "bidirectional"))
    )
    (net (code "9") (name "A5") (class "Default")
      (node (ref "U5") (pin "47") (pinfunction "PB02/I2/AIN10/SERCOM5.0_47") (pintype "bidirectional"))
    )
    (net (code "10") (name "AREF") (class "Default")
      (node (ref "C14") (pin "1") (pinfunction "1_1") (pintype "passive"))
      (node (ref "U5") (pin "4") (pinfunction "PA03/EINT3/VREFA/AIN1_4") (pintype "bidirectional"))
    )
    (net (code "11") (name "D+") (class "Default")
      (node (ref "CON1") (pin "D+") (pinfunction "D+_D+") (pintype "bidirectional"))
      (node (ref "U5") (pin "34") (pinfunction "PA25/I13/SERCOM3+5.3/D+_34") (pintype "bidirectional"))
    )
    (net (code "12") (name "D-") (class "Default")
      (node (ref "CON1") (pin "D-") (pinfunction "D-_D-") (pintype "bidirectional"))
      (node (ref "U5") (pin "33") (pinfunction "PA24/I12/SERCOM3+5.2/D-_33") (pintype "bidirectional"))
    )
    (net (code "13") (name "D0") (class "Default")
      (node (ref "U5") (pin "16") (pinfunction "PA11/I11/AIN19/SERCOM0+2.3/I2SF0_16") (pintype "bidirectional"))
      (node (ref "U6") (pin "2_TXD") (pinfunction "2_TXD_2_TXD") (pintype "bidirectional"))
    )
    (net (code "14") (name "D1") (class "Default")
      (node (ref "U5") (pin "15") (pinfunction "PA10/I10/AIN18/SERCOM0+2.2/I2SCK_15") (pintype "bidirectional"))
      (node (ref "U6") (pin "3_RXD") (pinfunction "3_RXD_3_RXD") (pintype "bidirectional"))
    )
    (net (code "15") (name "D2") (class "Default")
      (node (ref "U5") (pin "23") (pinfunction "PA14/I14/SERCOM2+4.2_23") (pintype "bidirectional"))
    )
    (net (code "16") (name "D3") (class "Default")
      (node (ref "U5") (pin "14") (pinfunction "PA09/I2C/I9/AIN17/SERCOM0+2.1/I2SMC_14") (pintype "bidirectional"))
    )
    (net (code "17") (name "D5") (class "Default")
      (node (ref "U3") (pin "4") (pinfunction "~{SHDN}_4") (pintype "input"))
      (node (ref "U5") (pin "24") (pinfunction "PA15/I15/SERCOM3+4.3_24") (pintype "bidirectional"))
    )
    (net (code "18") (name "D6") (class "Default")
      (node (ref "J1") (pin "5") (pinfunction "5_5") (pintype "bidirectional"))
      (node (ref "U5") (pin "29") (pinfunction "PA20/I4/SERCOM3+5.2/I2SSC_29") (pintype "bidirectional"))
    )
    (net (code "19") (name "D7") (class "Default")
      (node (ref "U5") (pin "30") (pinfunction "PA21/I5/SERCOM3+5.3/I2SFS0_30") (pintype "bidirectional"))
    )
    (net (code "20") (name "D8") (class "Default")
      (node (ref "U5") (pin "11") (pinfunction "PA06/EINT6/AIN6/SERCOM0.2_11") (pintype "bidirectional"))
    )
    (net (code "21") (name "D9") (class "Default")
      (node (ref "R3") (pin "2") (pinfunction "2_2") (pintype "passive"))
      (node (ref "R6") (pin "1") (pinfunction "1_1") (pintype "passive"))
      (node (ref "U5") (pin "12") (pinfunction "PA07/I7/AIN7/SERCOM0.3/I2SD0_12") (pintype "bidirectional"))
    )
    (net (code "22") (name "D10") (class "Default")
      (node (ref "J1") (pin "6") (pinfunction "6_6") (pintype "bidirectional"))
      (node (ref "U5") (pin "27") (pinfunction "PA18/I2/SERCOM1+3.2_27") (pintype "bidirectional"))
    )
    (net (code "23") (name "D11") (class "Default")
      (node (ref "Q1") (pin "1") (pinfunction "G_1") (pintype "passive"))
      (node (ref "R1") (pin "2") (pinfunction "2_2") (pintype "passive"))
      (node (ref "U5") (pin "25") (pinfunction "PA16/I2C/I0/SERCOM1+3.0_25") (pintype "bidirectional"))
    )
    (net (code "24") (name "D12") (class "Default")
      (node (ref "J1") (pin "7") (pinfunction "7_7") (pintype "bidirectional"))
      (node (ref "U5") (pin "28") (pinfunction "PA19/I3/SERCOM1+3.3/I2SD0_28") (pintype "bidirectional"))
    )
    (net (code "25") (name "D13") (class "Default")
      (node (ref "LED1") (pin "4") (pinfunction "DIN_4") (pintype "input"))
      (node (ref "R10") (pin "1") (pinfunction "1_1") (pintype "passive"))
      (node (ref "U5") (pin "26") (pinfunction "PA17/I2C/I1/SERCOM1+3.1_26") (pintype "bidirectional"))
    )
    (net (code "26") (name "GND") (class "Default")
      (node (ref "BAT3") (pin "GND@1") (pinfunction "-_GND@1") (pintype "power_in"))
      (node (ref "BAT3") (pin "GND@2") (pinfunction "-_GND@2") (pintype "power_in"))
      (node (ref "C1") (pin "2") (pinfunction "2_2") (pintype "passive"))
      (node (ref "C10") (pin "2") (pinfunction "2_2") (pintype "passive"))
      (node (ref "C12") (pin "-") (pinfunction "-_-") (pintype "passive"))
      (node (ref "C13") (pin "2") (pinfunction "2_2") (pintype "passive"))
      (node (ref "C14") (pin "2") (pinfunction "2_2") (pintype "passive"))
      (node (ref "C16") (pin "2") (pinfunction "2_2") (pintype "passive"))
      (node (ref "C17") (pin "2") (pinfunction "2_2") (pintype "passive"))
      (node (ref "C18") (pin "2") (pinfunction "2_2") (pintype "passive"))
      (node (ref "C19") (pin "2") (pinfunction "2_2") (pintype "passive"))
      (node (ref "C2") (pin "2") (pinfunction "2_2") (pintype "passive"))
      (node (ref "C3") (pin "2") (pinfunction "2_2") (pintype "passive"))
      (node (ref "C4") (pin "2") (pinfunction "2_2") (pintype "passive"))
      (node (ref "C5") (pin "2") (pinfunction "2_2") (pintype "passive"))
      (node (ref "C6") (pin "2") (pinfunction "2_2") (pintype "passive"))
      (node (ref "C7") (pin "2") (pinfunction "2_2") (pintype "passive"))
      (node (ref "C8") (pin "2") (pinfunction "2_2") (pintype "passive"))
      (node (ref "C9") (pin "2") (pinfunction "2_2") (pintype "passive"))
      (node (ref "CON1") (pin "BASE@1") (pinfunction "GND_BASE@1") (pintype "power_in"))
      (node (ref "CON1") (pin "BASE@2") (pinfunction "GND_BASE@2") (pintype "power_in"))
      (node (ref "CON1") (pin "GND") (pinfunction "GND_GND") (pintype "power_in"))
      (node (ref "CON1") (pin "SPRT@1") (pinfunction "GND_SPRT@1") (pintype "power_in"))
      (node (ref "CON1") (pin "SPRT@2") (pinfunction "GND_SPRT@2") (pintype "power_in"))
      (node (ref "CON1") (pin "SPRT@3") (pinfunction "GND_SPRT@3") (pintype "power_in"))
      (node (ref "CON1") (pin "SPRT@4") (pinfunction "GND_SPRT@4") (pintype "power_in"))
      (node (ref "CON4") (pin "1") (pinfunction "GND_1") (pintype "passive"))
      (node (ref "CON4") (pin "2") (pinfunction "GND_2") (pintype "passive"))
      (node (ref "GND") (pin "1") (pinfunction "1_1") (pintype "passive"))
      (node (ref "GND2") (pin "1") (pinfunction "1_1") (pintype "passive"))
      (node (ref "GND3") (pin "1") (pinfunction "1_1") (pintype "passive"))
      (node (ref "GNSS") (pin "G@1") (pinfunction "2_G@1") (pintype "passive"))
      (node (ref "GNSS") (pin "G@2") (pinfunction "2_G@2") (pintype "passive"))
      (node (ref "GNSS") (pin "G@3") (pinfunction "2_G@3") (pintype "passive"))
      (node (ref "GNSS") (pin "G@4") (pinfunction "2_G@4") (pintype "passive"))
      (node (ref "IRIDIUM") (pin "G@1") (pinfunction "2_G@1") (pintype "passive"))
      (node (ref "IRIDIUM") (pin "G@2") (pinfunction "2_G@2") (pintype "passive"))
      (node (ref "IRIDIUM") (pin "G@3") (pinfunction "2_G@3") (pintype "passive"))
      (node (ref "IRIDIUM") (pin "G@4") (pinfunction "2_G@4") (pintype "passive"))
      (node (ref "J1") (pin "13") (pinfunction "13_13") (pintype "bidirectional"))
      (node (ref "J1") (pin "14") (pinfunction "14_14") (pintype "bidirectional"))
      (node (ref "J1") (pin "15") (pinfunction "15_15") (pintype "bidirectional"))
      (node (ref "J1") (pin "18") (pinfunction "18_18") (pintype "bidirectional"))
      (node (ref "J1") (pin "3") (pinfunction "3_3") (pintype "bidirectional"))
      (node (ref "J1") (pin "4") (pinfunction "4_4") (pintype "bidirectional"))
      (node (ref "J1") (pin "8") (pinfunction "8_8") (pintype "bidirectional"))
      (node (ref "JP1") (pin "1") (pinfunction "1_1") (pintype "passive"))
      (node (ref "LED1") (pin "3") (pinfunction "VSS_3") (pintype "power_in"))
      (node (ref "LED2") (pin "C") (pinfunction "C_C") (pintype "passive"))
      (node (ref "R1") (pin "1") (pinfunction "1_1") (pintype "passive"))
      (node (ref "R11") (pin "1") (pinfunction "1_1") (pintype "passive"))
      (node (ref "R2") (pin "1") (pinfunction "1_1") (pintype "passive"))
      (node (ref "R6") (pin "2") (pinfunction "2_2") (pintype "passive"))
      (node (ref "S1") (pin "P1") (pinfunction "P$1_P1") (pintype "bidirectional"))
      (node (ref "S2") (pin "P1") (pinfunction "P$1_P1") (pintype "bidirectional"))
      (node (ref "SOLAR1-") (pin "1") (pinfunction "1_1") (pintype "passive"))
      (node (ref "SOLAR2-") (pin "1") (pinfunction "1_1") (pintype "passive"))
      (node (ref "SW1") (pin "3") (pinfunction "3_3") (pintype "passive"))
      (node (ref "SW1") (pin "4") (pinfunction "4_4") (pintype "passive"))
      (node (ref "U1") (pin "2") (pinfunction "VSS_2") (pintype "power_in"))
      (node (ref "U2") (pin "2") (pinfunction "GND_2") (pintype "power_in"))
      (node (ref "U3") (pin "11") (pinfunction "GND_2_11") (pintype "passive"))
      (node (ref "U3") (pin "8") (pinfunction "GND_8") (pintype "passive"))
      (node (ref "U4") (pin "3") (pinfunction "GND_3") (pintype "power_in"))
      (node (ref "U5") (pin "18") (pinfunction "GND_18") (pintype "power_in"))
      (node (ref "U5") (pin "35") (pinfunction "GND_35") (pintype "power_in"))
      (node (ref "U5") (pin "42") (pinfunction "GND_42") (pintype "power_in"))
      (node (ref "U5") (pin "5") (pinfunction "GNDA_5") (pintype "power_in"))
      (node (ref "U5") (pin "THERMAL") (pinfunction "GND_THERMAL") (pintype "power_in"))
      (node (ref "U6") (pin "10_GND") (pinfunction "10_GND_10_GND") (pintype "power_in"))
      (node (ref "U6") (pin "12_GND") (pinfunction "12_GND_12_GND") (pintype "power_in"))
      (node (ref "U6") (pin "1_GND") (pinfunction "1_GND_1_GND") (pintype "power_in"))
      (node (ref "U7") (pin "4") (pinfunction "GND_4") (pintype "passive"))
    )
    (net (code "27") (name "GPS_ANT") (class "Default")
      (node (ref "GNSS") (pin "1") (pinfunction "1_1") (pintype "passive"))
      (node (ref "L1") (pin "2") (pinfunction "P$2_2") (pintype "passive"))
      (node (ref "U6") (pin "11_RF_IN") (pinfunction "11_RF_IN_11_RF_IN") (pintype "bidirectional"))
    )
    (net (code "28") (name "LTC3225_VOUT") (class "Default")
      (node (ref "C11") (pin "+") (pinfunction "+_+") (pintype "passive"))
      (node (ref "C16") (pin "1") (pinfunction "1_1") (pintype "passive"))
      (node (ref "J1") (pin "1") (pinfunction "1_1") (pintype "bidirectional"))
      (node (ref "J1") (pin "2") (pinfunction "2_2") (pintype "bidirectional"))
      (node (ref "U3") (pin "10") (pinfunction "COUT_10") (pintype "output"))
    )
    (net (code "29") (name "MISO") (class "Default")
      (node (ref "MISO") (pin "1") (pinfunction "1_1") (pintype "passive"))
      (node (ref "U5") (pin "21") (pinfunction "PA12/I12/I2C/SERCOM2+4.0_21") (pintype "bidirectional"))
    )
    (net (code "30") (name "MOSI") (class "Default")
      (node (ref "MOSI") (pin "1") (pinfunction "1_1") (pintype "passive"))
      (node (ref "U5") (pin "19") (pinfunction "PB10/I10/SERCOM4.2/I2SMC_19") (pintype "bidirectional"))
    )
    (net (code "31") (name "Net-(BAT1---PadGND@1)") (class "Default")
      (node (ref "BAT1") (pin "GND@1") (pinfunction "-_GND@1") (pintype "power_in"))
      (node (ref "BAT1") (pin "GND@2") (pinfunction "-_GND@2") (pintype "power_in"))
      (node (ref "BAT2") (pin "PWR@1") (pinfunction "+_PWR@1") (pintype "power_in"))
      (node (ref "BAT2") (pin "PWR@2") (pinfunction "+_PWR@2") (pintype "power_in"))
    )
    (net (code "32") (name "Net-(BAT2---PadGND@1)") (class "Default")
      (node (ref "BAT2") (pin "GND@1") (pinfunction "-_GND@1") (pintype "power_in"))
      (node (ref "BAT2") (pin "GND@2") (pinfunction "-_GND@2") (pintype "power_in"))
      (node (ref "BAT3") (pin "PWR@1") (pinfunction "+_PWR@1") (pintype "power_in"))
      (node (ref "BAT3") (pin "PWR@2") (pinfunction "+_PWR@2") (pintype "power_in"))
    )
    (net (code "33") (name "Net-(CON1-PadVBUS)") (class "Default")
      (node (ref "CON1") (pin "VBUS") (pinfunction "VBUS_VBUS") (pintype "power_in"))
      (node (ref "D4") (pin "A") (pinfunction "A_A") (pintype "passive"))
    )
    (net (code "34") (name "Net-(CON4-SIGNAL)") (class "Default")
      (node (ref "CON4") (pin "3") (pinfunction "SIGNAL_3") (pintype "passive"))
      (node (ref "IRIDIUM") (pin "1") (pinfunction "1_1") (pintype "passive"))
    )
    (net (code "35") (name "Net-(D2-PadA)") (class "Default")
      (node (ref "D2") (pin "A") (pinfunction "A_A") (pintype "passive"))
      (node (ref "SOLAR2+") (pin "1") (pinfunction "1_1") (pintype "passive"))
    )
    (net (code "36") (name "Net-(D3-PadA)") (class "Default")
      (node (ref "D3") (pin "A") (pinfunction "A_A") (pintype "passive"))
      (node (ref "SOLAR1+") (pin "1") (pinfunction "1_1") (pintype "passive"))
    )
    (net (code "37") (name "Net-(JP2-Pad1)") (class "Default")
      (node (ref "JP2") (pin "1") (pinfunction "1_1") (pintype "passive"))
      (node (ref "R11") (pin "2") (pinfunction "2_2") (pintype "passive"))
    )
    (net (code "38") (name "Net-(JP2-Pad3)") (class "Default")
      (node (ref "JP2") (pin "3") (pinfunction "3_3") (pintype "passive"))
      (node (ref "R2") (pin "2") (pinfunction "2_2") (pintype "passive"))
    )
    (net (code "39") (name "Net-(L1-P$1)") (class "Default")
      (node (ref "C18") (pin "1") (pinfunction "1_1") (pintype "passive"))
      (node (ref "L1") (pin "1") (pinfunction "P$1_1") (pintype "passive"))
      (node (ref "R9") (pin "1") (pinfunction "1_1") (pintype "passive"))
    )
    (net (code "40") (name "Net-(LED2-PadA)") (class "Default")
      (node (ref "LED2") (pin "A") (pinfunction "A_A") (pintype "passive"))
      (node (ref "R10") (pin "2") (pinfunction "2_2") (pintype "passive"))
    )
    (net (code "41") (name "Net-(U3-C+)") (class "Default")
      (node (ref "C15") (pin "1") (pinfunction "1_1") (pintype "passive"))
      (node (ref "U3") (pin "1") (pinfunction "C+_1") (pintype "passive"))
    )
    (net (code "42") (name "Net-(U3-C-)") (class "Default")
      (node (ref "C15") (pin "2") (pinfunction "2_2") (pintype "passive"))
      (node (ref "U3") (pin "2") (pinfunction "C-_2") (pintype "passive"))
    )
    (net (code "43") (name "Net-(U3-CX)") (class "Default")
      (node (ref "C11") (pin "-") (pinfunction "-_-") (pintype "passive"))
      (node (ref "C12") (pin "+") (pinfunction "+_+") (pintype "passive"))
      (node (ref "U3") (pin "3") (pinfunction "CX_3") (pintype "passive"))
    )
    (net (code "44") (name "Net-(U3-PROG)") (class "Default")
      (node (ref "JP2") (pin "2") (pinfunction "2_2") (pintype "passive"))
      (node (ref "U3") (pin "7") (pinfunction "PROG_7") (pintype "input"))
    )
    (net (code "45") (name "Net-(U3-VSEL)") (class "Default")
      (node (ref "JP1") (pin "2") (pinfunction "2_2") (pintype "passive"))
      (node (ref "U3") (pin "6") (pinfunction "VSEL_6") (pintype "input"))
    )
    (net (code "46") (name "Net-(U4-CAP)") (class "Default")
      (node (ref "C13") (pin "1") (pinfunction "1_1") (pintype "passive"))
      (node (ref "U4") (pin "2") (pinfunction "CAP_2") (pintype "power_in"))
    )
    (net (code "47") (name "Net-(U5-PA00{slash}EINT0{slash}SERCOM1.0)") (class "Default")
      (node (ref "C2") (pin "1") (pinfunction "1_1") (pintype "passive"))
      (node (ref "U5") (pin "1") (pinfunction "PA00/EINT0/SERCOM1.0_1") (pintype "bidirectional"))
      (node (ref "X1") (pin "P$1") (pinfunction "P$1_P$1") (pintype "bidirectional"))
    )
    (net (code "48") (name "Net-(U5-PA01{slash}EINT1{slash}SERCOM1.1)") (class "Default")
      (node (ref "C4") (pin "1") (pinfunction "1_1") (pintype "passive"))
      (node (ref "U5") (pin "2") (pinfunction "PA01/EINT1/SERCOM1.1_2") (pintype "bidirectional"))
      (node (ref "X1") (pin "P$2") (pinfunction "P$2_P$2") (pintype "bidirectional"))
    )
    (net (code "49") (name "Net-(U5-VDDCORE)") (class "Default")
      (node (ref "C1") (pin "1") (pinfunction "1_1") (pintype "passive"))
      (node (ref "U5") (pin "43") (pinfunction "VDDCORE_43") (pintype "power_in"))
    )
    (net (code "50") (name "SCK") (class "Default")
      (node (ref "SCK") (pin "1") (pinfunction "1_1") (pintype "passive"))
      (node (ref "U5") (pin "20") (pinfunction "PB11/I11/SERCOM4.3/I2SCL_20") (pintype "bidirectional"))
    )
    (net (code "51") (name "SCL") (class "Default")
      (node (ref "R8") (pin "2") (pinfunction "2_2") (pintype "passive"))
      (node (ref "SCL") (pin "1") (pinfunction "1_1") (pintype "passive"))
      (node (ref "U4") (pin "8") (pinfunction "SCL_8") (pintype "bidirectional"))
      (node (ref "U5") (pin "32") (pinfunction "PA23/I2C/I7/SERCOM3+5.1/SOF_32") (pintype "bidirectional"))
    )
    (net (code "52") (name "SDA") (class "Default")
      (node (ref "R5") (pin "2") (pinfunction "2_2") (pintype "passive"))
      (node (ref "SDA") (pin "1") (pinfunction "1_1") (pintype "passive"))
      (node (ref "U4") (pin "7") (pinfunction "SDA_7") (pintype "bidirectional"))
      (node (ref "U5") (pin "31") (pinfunction "PA22/I2C/I6/SERCOM3+5.0_31") (pintype "bidirectional"))
    )
    (net (code "53") (name "SD_CS") (class "Default")
      (node (ref "SD_CS") (pin "1") (pinfunction "1_1") (pintype "passive"))
      (node (ref "U5") (pin "13") (pinfunction "PA08/I2C/AIN16/SERCOM0+2.0/I2SD1_13") (pintype "bidirectional"))
    )
    (net (code "54") (name "SWCLK") (class "Default")
      (node (ref "SWCLK") (pin "1") (pinfunction "1_1") (pintype "passive"))
      (node (ref "U5") (pin "45") (pinfunction "PA30/I10/SECOM1.2/SWCLK_45") (pintype "bidirectional"))
    )
    (net (code "55") (name "SWDIO") (class "Default")
      (node (ref "SWDIO") (pin "1") (pinfunction "1_1") (pintype "passive"))
      (node (ref "U5") (pin "46") (pinfunction "PA31/I11/SECOM1.3/SWDIO_46") (pintype "bidirectional"))
    )
    (net (code "56") (name "VBAT") (class "Default")
      (node (ref "BAT1") (pin "PWR@1") (pinfunction "+_PWR@1") (pintype "power_in"))
      (node (ref "BAT1") (pin "PWR@2") (pinfunction "+_PWR@2") (pintype "power_in"))
      (node (ref "D1") (pin "A") (pinfunction "A_A") (pintype "passive"))
    )
    (net (code "57") (name "VBUS") (class "Default")
      (node (ref "C17") (pin "1") (pinfunction "1_1") (pintype "passive"))
      (node (ref "C6") (pin "1") (pinfunction "1_1") (pintype "passive"))
      (node (ref "D1") (pin "C") (pinfunction "C_C") (pintype "passive"))
      (node (ref "D2") (pin "C") (pinfunction "C_C") (pintype "passive"))
      (node (ref "D3") (pin "C") (pinfunction "C_C") (pintype "passive"))
      (node (ref "D4") (pin "C") (pinfunction "C_C") (pintype "passive"))
      (node (ref "JP1") (pin "3") (pinfunction "3_3") (pintype "passive"))
      (node (ref "R3") (pin "1") (pinfunction "1_1") (pintype "passive"))
      (node (ref "R7") (pin "1") (pinfunction "1_1") (pintype "passive"))
      (node (ref "U2") (pin "1") (pinfunction "IN_1") (pintype "power_in"))
      (node (ref "U2") (pin "3") (pinfunction "EN_3") (pintype "input"))
      (node (ref "U3") (pin "9") (pinfunction "VIN_9") (pintype "power_in"))
      (node (ref "VBUS") (pin "1") (pinfunction "1_1") (pintype "passive"))
    )
    (net (code "58") (name "VCC_RF") (class "Default")
      (node (ref "R9") (pin "2") (pinfunction "2_2") (pintype "passive"))
      (node (ref "U6") (pin "14_VCC_RF") (pinfunction "14_VCC_RF_14_VCC_RF") (pintype "bidirectional"))
    )
    (net (code "59") (name "unconnected-(CON1-PadID)") (class "Default")
      (node (ref "CON1") (pin "ID") (pinfunction "ID_ID") (pintype "bidirectional"))
    )
    (net (code "60") (name "unconnected-(J1-Pad9)") (class "Default")
      (node (ref "J1") (pin "9") (pinfunction "9_9") (pintype "bidirectional"))
    )
    (net (code "61") (name "unconnected-(J1-Pad10)") (class "Default")
      (node (ref "J1") (pin "10") (pinfunction "10_10") (pintype "bidirectional"))
    )
    (net (code "62") (name "unconnected-(J1-Pad11)") (class "Default")
      (node (ref "J1") (pin "11") (pinfunction "11_11") (pintype "bidirectional"))
    )
    (net (code "63") (name "unconnected-(J1-Pad12)") (class "Default")
      (node (ref "J1") (pin "12") (pinfunction "12_12") (pintype "bidirectional"))
    )
    (net (code "64") (name "unconnected-(J1-Pad16)") (class "Default")
      (node (ref "J1") (pin "16") (pinfunction "16_16") (pintype "bidirectional"))
    )
    (net (code "65") (name "unconnected-(J1-Pad17)") (class "Default")
      (node (ref "J1") (pin "17") (pinfunction "17_17") (pintype "bidirectional"))
    )
    (net (code "66") (name "unconnected-(J1-Pad20)") (class "Default")
      (node (ref "J1") (pin "20") (pinfunction "20_20") (pintype "bidirectional"))
    )
    (net (code "67") (name "unconnected-(LED1-DOUT-Pad2)") (class "Default")
      (node (ref "LED1") (pin "2") (pinfunction "DOUT_2") (pintype "output"))
    )
    (net (code "68") (name "unconnected-(U2-P4-Pad4)") (class "Default")
      (node (ref "U2") (pin "4") (pinfunction "P4_4") (pintype "bidirectional"))
    )
    (net (code "69") (name "unconnected-(U4-INT1-Pad6)") (class "Default")
      (node (ref "U4") (pin "6") (pinfunction "INT1_6") (pintype "output"))
    )
    (net (code "70") (name "unconnected-(U4-INT2-Pad5)") (class "Default")
      (node (ref "U4") (pin "5") (pinfunction "INT2_5") (pintype "output"))
    )
    (net (code "71") (name "unconnected-(U5-PA13{slash}I13{slash}I2C{slash}SERCOM2+4.1-Pad22)") (class "Default")
      (node (ref "U5") (pin "22") (pinfunction "PA13/I13/I2C/SERCOM2+4.1_22") (pintype "bidirectional"))
    )
    (net (code "72") (name "unconnected-(U5-PA27{slash}I15-Pad39)") (class "Default")
      (node (ref "U5") (pin "39") (pinfunction "PA27/I15_39") (pintype "bidirectional"))
    )
    (net (code "73") (name "unconnected-(U5-PA28{slash}I8-Pad41)") (class "Default")
      (node (ref "U5") (pin "41") (pinfunction "PA28/I8_41") (pintype "bidirectional"))
    )
    (net (code "74") (name "unconnected-(U5-PB03{slash}I3{slash}AIN11{slash}SERCOM5.1-Pad48)") (class "Default")
      (node (ref "U5") (pin "48") (pinfunction "PB03/I3/AIN11/SERCOM5.1_48") (pintype "bidirectional"))
    )
    (net (code "75") (name "unconnected-(U5-PB22{slash}I6{slash}SERCOM5.2-Pad37)") (class "Default")
      (node (ref "U5") (pin "37") (pinfunction "PB22/I6/SERCOM5.2_37") (pintype "bidirectional"))
    )
    (net (code "76") (name "unconnected-(U5-PB23{slash}I7{slash}SERCOM5.3-Pad38)") (class "Default")
      (node (ref "U5") (pin "38") (pinfunction "PB23/I7/SERCOM5.3_38") (pintype "bidirectional"))
    )
    (net (code "77") (name "unconnected-(U6-13_LNA_EN{slash}RES-Pad13_LNA_EN)") (class "Default")
      (node (ref "U6") (pin "13_LNA_EN") (pinfunction "13_LNA_EN/RES_13_LNA_EN") (pintype "bidirectional"))
    )
    (net (code "78") (name "unconnected-(U6-15_RES{slash}V_ANT-Pad15_V_ANT{slash}RESERVED)") (class "Default")
      (node (ref "U6") (pin "15_V_ANT/RESERVED") (pinfunction "15_RES/V_ANT_15_V_ANT/RESERVED") (pintype "bidirectional"))
    )
    (net (code "79") (name "unconnected-(U6-Pad4_TIMEPULSE)") (class "Default")
      (node (ref "U6") (pin "4_TIMEPULSE") (pinfunction "4_TIMEPULSE_4_TIMEPULSE") (pintype "bidirectional"))
    )
    (net (code "80") (name "unconnected-(U6-Pad5_EXTINT)") (class "Default")
      (node (ref "U6") (pin "5_EXTINT") (pinfunction "5_EXTINT_5_EXTINT") (pintype "bidirectional"))
    )
    (net (code "81") (name "unconnected-(U6-Pad16_SDA)") (class "Default")
      (node (ref "U6") (pin "16_SDA") (pinfunction "16_SDA_16_SDA") (pintype "bidirectional"))
    )
    (net (code "82") (name "unconnected-(U6-Pad17_SCL)") (class "Default")
      (node (ref "U6") (pin "17_SCL") (pinfunction "17_SCL_17_SCL") (pintype "bidirectional"))
    )
    (net (code "83") (name "unconnected-(U6-Pad18_SAFEBOOT_N)") (class "Default")
      (node (ref "U6") (pin "18_SAFEBOOT_N") (pinfunction "18_SAFEBOOT_N_18_SAFEBOOT_N") (pintype "bidirectional"))
    )
    (net (code "84") (name "~{RESET}") (class "Default")
      (node (ref "SW1") (pin "1") (pinfunction "1_1") (pintype "passive"))
      (node (ref "SW1") (pin "2") (pinfunction "2_2") (pintype "passive"))
      (node (ref "U1") (pin "1") (pinfunction "VOUT_1") (pintype "output"))
      (node (ref "U5") (pin "40") (pinfunction "/RESET_40") (pintype "bidirectional"))
    )
  )
)
